# SF16_POWER.net
KiCad netlist of a schematic drawn in Altium Designer
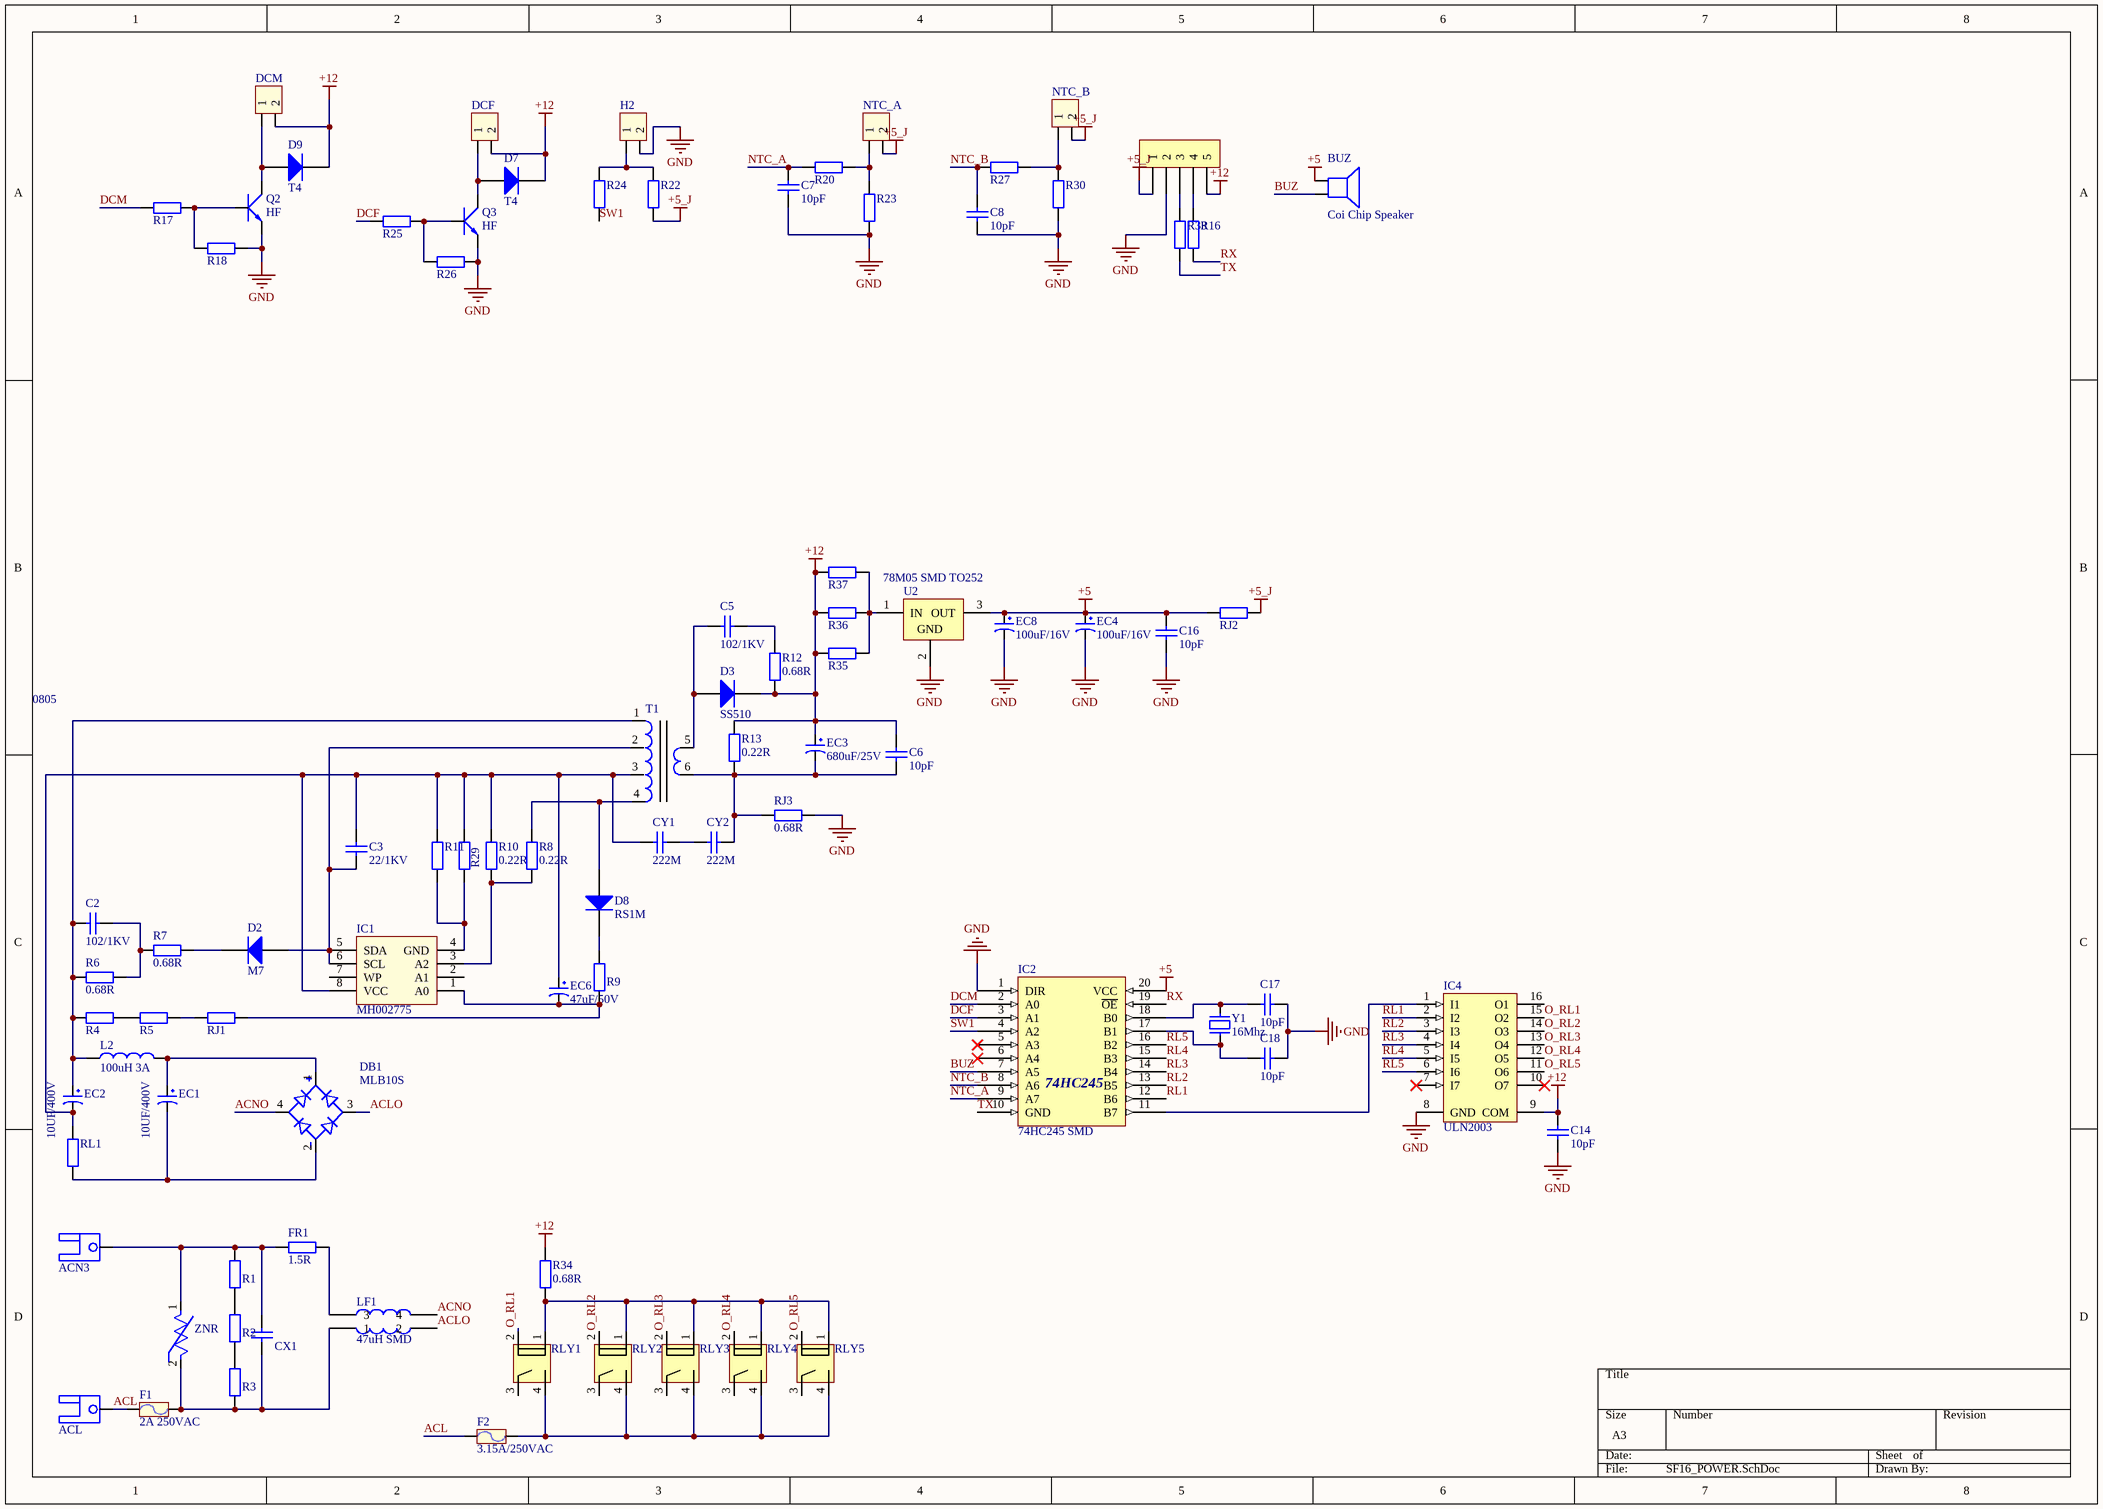
[diagram p0: SF16_POWER.SchDoc]

(export (version "E")
  (design (tool "Eeschema 10.0.6"))
  (components
    (comp (ref "ACL")
      (value "1217861-1")
      (footprint "CON1_P192_70D137_TH_ST")
      (description "1 Pins, 1 Row 256mil Pitch, Straight, Male")
      (fields
        (field (name "MANUFACTURER") "TE Connectivity")
        (field (name "MATING PART NUMBER") "2-520183-2")
      )
      (libsource (lib "Connector") (part "CON-PLG-SPADE_1X1-256-ST-TH"))
    )
    (comp (ref "ACN3")
      (value "1217861-1")
      (footprint "CON1_P192_70D137_TH_ST")
      (description "1 Pins, 1 Row 256mil Pitch, Straight, Male")
      (fields
        (field (name "MANUFACTURER") "TE Connectivity")
        (field (name "MATING PART NUMBER") "2-520183-2")
      )
      (libsource (lib "Connector") (part "CON-PLG-SPADE_1X1-256-ST-TH"))
    )
    (comp (ref "BUZ")
      (value "Coi Chip Speaker")
      (footprint "Coi 14mm")
      (description "Còi chip")
      (libsource (lib "Component") (part "Coi 14mm"))
    )
    (comp (ref "C2")
      (value "102/1KV")
      (footprint "TU GOM CAO AP")
      (description "Cắm")
      (libsource (lib "Tu dien") (part "Tu gom CAO AP"))
    )
    (comp (ref "C3")
      (value "22/1KV")
      (footprint "TU GOM CAO AP")
      (description "Cắm")
      (libsource (lib "Tu dien") (part "Tu gom CAO AP"))
    )
    (comp (ref "C5")
      (value "102/1KV")
      (footprint "TU GOM CAO AP")
      (description "Cắm")
      (libsource (lib "Tu dien") (part "Tu gom CAO AP"))
    )
    (comp (ref "C6")
      (value "10pF")
      (footprint "tu 0805")
      (description "Dán")
      (libsource (lib "Tu dien") (part "Tu 0805 10pF 50V 10%"))
    )
    (comp (ref "C7")
      (value "10pF")
      (footprint "tu 0805")
      (description "Dán")
      (libsource (lib "Tu dien") (part "Tu 0805 10pF 50V 10%"))
    )
    (comp (ref "C8")
      (value "10pF")
      (footprint "tu 0805")
      (description "Dán")
      (libsource (lib "Tu dien") (part "Tu 0805 10pF 50V 10%"))
    )
    (comp (ref "C14")
      (value "10pF")
      (footprint "tu 0805")
      (description "Dán")
      (libsource (lib "Tu dien") (part "Tu 0805 10pF 50V 10%"))
    )
    (comp (ref "C16")
      (value "10pF")
      (footprint "tu 0805")
      (description "Dán")
      (libsource (lib "Tu dien") (part "Tu 0805 10pF 50V 10%"))
    )
    (comp (ref "C17")
      (value "10pF")
      (footprint "tu 0805")
      (description "Dán")
      (libsource (lib "Tu dien") (part "Tu 0805 10pF 50V 10%"))
    )
    (comp (ref "C18")
      (value "10pF")
      (footprint "tu 0805")
      (description "Dán")
      (libsource (lib "Tu dien") (part "Tu 0805 10pF 50V 10%"))
    )
    (comp (ref "CX1")
      (value "0.1")
      (footprint "Tu vuong 10mm")
      (description "Cắm")
      (libsource (lib "Tu dien") (part "Tu MKP X2 0.1uF 275VAC 10MM"))
    )
    (comp (ref "CY1")
      (value "222M")
      (footprint "TU GOM CAO AP 222M")
      (description "Cắm")
      (libsource (lib "Tu dien") (part "Tu gom CAO AP 222M"))
    )
    (comp (ref "CY2")
      (value "222M")
      (footprint "TU GOM CAO AP 222M")
      (description "Cắm")
      (libsource (lib "Tu dien") (part "Tu gom CAO AP 222M"))
    )
    (comp (ref "D2")
      (value "M7")
      (footprint "DIODE SMA")
      (description "Dán")
      (libsource (lib "Diode") (part "Diode M7 1N4007 SMD 1A 1000V"))
    )
    (comp (ref "D3")
      (value "SS510")
      (footprint "DIODE SMA")
      (description "Dán")
      (libsource (lib "Diode") (part "Diode SS34 ( 1N5822 )"))
    )
    (comp (ref "D7")
      (value "T4")
      (footprint "DIODE SOD-123")
      (description "Dán")
      (libsource (lib "Diode") (part "Diode S4"))
    )
    (comp (ref "D8")
      (value "RS1M")
      (footprint "DIODE SMA")
      (description "Dán")
      (libsource (lib "Diode") (part "Diode SS34 ( 1N5822 )"))
    )
    (comp (ref "D9")
      (value "T4")
      (footprint "DIODE SOD-123")
      (description "Dán")
      (libsource (lib "Diode") (part "Diode S4"))
    )
    (comp (ref "DB1")
      (value "MLB10S")
      (footprint "MBLS-1")
      (description "DÁN")
      (libsource (lib "Diode") (part "MLB10S"))
    )
    (comp (ref "DCF")
      (value "Header 2P 2.54 Duc Thang")
      (footprint "XH2.54M-2")
      (description "Cắm")
      (libsource (lib "Header") (part "Header 2P 2.54 Duc Thang"))
    )
    (comp (ref "DCM")
      (value "Header 2P 2.54 Duc Thang")
      (footprint "XH2.54M-2")
      (description "Cắm")
      (libsource (lib "Header") (part "Header 2P 2.54 Duc Thang"))
    )
    (comp (ref "EC1")
      (value "10UF/400V")
      (footprint "tu hoa 10mm")
      (description "Cắm")
      (libsource (lib "Tu dien") (part "Tu Hoa 1000uF 10V 10x12"))
    )
    (comp (ref "EC2")
      (value "10UF/400V")
      (footprint "tu hoa 10mm")
      (description "Cắm")
      (libsource (lib "Tu dien") (part "Tu Hoa 1000uF 10V 10x12"))
    )
    (comp (ref "EC3")
      (value "680uF/25V")
      (footprint "tu hoa 10mm")
      (description "Cắm")
      (libsource (lib "Tu dien") (part "Tu Hoa 6.8uF 400V 10x17"))
    )
    (comp (ref "EC4")
      (value "100uF/16V")
      (footprint "tu hoa 5mm")
      (description "Cắm")
      (libsource (lib "Tu dien") (part "Tu Hoa 330uF 10V 6x11"))
    )
    (comp (ref "EC6")
      (value "47uF/50V")
      (footprint "tu hoa 5mm")
      (description "Cắm")
      (libsource (lib "Tu dien") (part "Tu Hoa 47uF 16V 5x10"))
    )
    (comp (ref "EC8")
      (value "100uF/16V")
      (footprint "tu hoa 5mm")
      (description "Cắm")
      (libsource (lib "Tu dien") (part "Tu Hoa 330uF 10V 6x11"))
    )
    (comp (ref "F1")
      (value "2A 250VAC")
      (footprint "Cau chi 2A 250V T2A250V")
      (description "Cắm")
      (libsource (lib "Component") (part "Cau chi 2A 250V T2A250V"))
    )
    (comp (ref "F2")
      (value "3.15A/250VAC")
      (footprint "Cau Chi 250V")
      (description "Cắm")
      (libsource (lib "Component") (part "Cau chi 2A 250V T2A250V"))
    )
    (comp (ref "FR1")
      (value "1.5R")
      (footprint "TRO CAU CHI DUNG")
      (description "Cắm")
      (libsource (lib "Dien Tro") (part "Tro Vach 2W"))
    )
    (comp (ref "H2")
      (value "Header 2P 2.54 Duc Thang")
      (footprint "XH2.54M-2")
      (description "Cắm")
      (libsource (lib "Header") (part "Header 2P 2.54 Duc Thang"))
    )
    (comp (ref "H5")
      (value "Header 5P 2.54 DT")
      (footprint "XH2.54M-5")
      (description "Cắm")
      (libsource (lib "Header") (part "Header 5P 2.54 DT"))
    )
    (comp (ref "IC1")
      (value "MH002775")
      (footprint "DIP8")
      (description "Cắm")
      (libsource (lib "IC") (part "AT24C01 DIP8 EEPROM"))
    )
    (comp (ref "IC2")
      (value "74HC245 SMD")
      (footprint "SOP 20")
      (description "Dán")
      (libsource (lib "IC") (part "74HC245 SMD"))
    )
    (comp (ref "IC4")
      (value "ULN2003")
      (footprint "SOP 16")
      (description "Dán")
      (libsource (lib "IC") (part "ULN2003A SMD"))
    )
    (comp (ref "L2")
      (value "100uH 3A")
      (footprint "CUON CAM - duplicate")
      (description "Dán")
      (libsource (lib "Cuon Cam") (part "CUON CAM VACH DUNG"))
    )
    (comp (ref "LF1")
      (value "47uH SMD")
      (footprint "Cuon Cam AC-AC")
      (description "Dán")
      (libsource (lib "Cuon Cam") (part "CUON CAM AC_AC"))
    )
    (comp (ref "NTC_A")
      (value "Header 2P 2.54 Duc Thang")
      (footprint "XH2.54M-2")
      (description "Cắm")
      (libsource (lib "Header") (part "Header 2P 2.54 Duc Thang"))
    )
    (comp (ref "NTC_B")
      (value "Header 2P 2.54 Duc Thang")
      (footprint "XH2.54M-2")
      (description "Cắm")
      (libsource (lib "Header") (part "Header 2P 2.54 Duc Thang"))
    )
    (comp (ref "Q2")
      (value "HF")
      (footprint "SOT-23")
      (description "Cắm")
      (libsource (lib "TranFet") (part "C1815 SOT23 TRANS NPN 0.15A 50V"))
    )
    (comp (ref "Q3")
      (value "HF")
      (footprint "SOT-23")
      (description "Cắm")
      (libsource (lib "TranFet") (part "C1815 SOT23 TRANS NPN 0.15A 50V"))
    )
    (comp (ref "R1")
      (value "0.68R")
      (footprint "tro smd 1206")
      (description "Dán")
      (libsource (lib "Dien Tro") (part "Tro 1206"))
    )
    (comp (ref "R2")
      (value "0.68R")
      (footprint "tro smd 1206")
      (description "Dán")
      (libsource (lib "Dien Tro") (part "Tro 1206"))
    )
    (comp (ref "R3")
      (value "0.68R")
      (footprint "tro smd 1206")
      (description "Dán")
      (libsource (lib "Dien Tro") (part "Tro 1206"))
    )
    (comp (ref "R4")
      (value "0.68R")
      (footprint "tro smd 1206")
      (description "Dán")
      (libsource (lib "Dien Tro") (part "Tro 1206"))
    )
    (comp (ref "R5")
      (value "0.68R")
      (footprint "tro smd 1206")
      (description "Dán")
      (libsource (lib "Dien Tro") (part "Tro 1206"))
    )
    (comp (ref "R6")
      (value "0.68R")
      (footprint "tro smd 1206")
      (description "Dán")
      (libsource (lib "Dien Tro") (part "Tro 1206"))
    )
    (comp (ref "R7")
      (value "0.68R")
      (footprint "tro smd 1206")
      (description "Dán")
      (libsource (lib "Dien Tro") (part "Tro 1206"))
    )
    (comp (ref "R8")
      (value "0.22R")
      (footprint "tro smd 0805")
      (description "Dán")
      (libsource (lib "Dien Tro") (part "Tro 0805"))
    )
    (comp (ref "R9")
      (value "0.68R")
      (footprint "tro smd 1206")
      (description "Dán")
      (libsource (lib "Dien Tro") (part "Tro 1206"))
    )
    (comp (ref "R10")
      (value "0.22R")
      (footprint "tro smd 0805")
      (description "Dán")
      (libsource (lib "Dien Tro") (part "Tro 0805"))
    )
    (comp (ref "R11")
      (value "0.68R")
      (footprint "tro smd 1206")
      (description "Dán")
      (libsource (lib "Dien Tro") (part "Tro 1206"))
    )
    (comp (ref "R12")
      (value "0.68R")
      (footprint "tro smd 1206")
      (description "Dán")
      (libsource (lib "Dien Tro") (part "Tro 1206"))
    )
    (comp (ref "R13")
      (value "0.22R")
      (footprint "tro smd 0805")
      (description "Dán")
      (libsource (lib "Dien Tro") (part "Tro 0805"))
    )
    (comp (ref "R16")
      (value "0.22R")
      (footprint "tro smd 0805")
      (description "Dán")
      (libsource (lib "Dien Tro") (part "Tro 0805"))
    )
    (comp (ref "R17")
      (value "0.68R")
      (footprint "tro smd 1206")
      (description "Dán")
      (libsource (lib "Dien Tro") (part "Tro 1206"))
    )
    (comp (ref "R18")
      (value "0.22R")
      (footprint "tro smd 0805")
      (description "Dán")
      (libsource (lib "Dien Tro") (part "Tro 0805"))
    )
    (comp (ref "R20")
      (value "0.22R")
      (footprint "tro smd 0805")
      (description "Dán")
      (libsource (lib "Dien Tro") (part "Tro 0805"))
    )
    (comp (ref "R22")
      (value "0.22R")
      (footprint "tro smd 0805")
      (description "Dán")
      (libsource (lib "Dien Tro") (part "Tro 0805"))
    )
    (comp (ref "R23")
      (value "0.22R")
      (footprint "tro smd 0805")
      (description "Dán")
      (libsource (lib "Dien Tro") (part "Tro 0805"))
    )
    (comp (ref "R24")
      (value "0.22R")
      (footprint "tro smd 0805")
      (description "Dán")
      (libsource (lib "Dien Tro") (part "Tro 0805"))
    )
    (comp (ref "R25")
      (value "0.68R")
      (footprint "tro smd 1206")
      (description "Dán")
      (libsource (lib "Dien Tro") (part "Tro 1206"))
    )
    (comp (ref "R26")
      (value "0.22R")
      (footprint "tro smd 0805")
      (description "Dán")
      (libsource (lib "Dien Tro") (part "Tro 0805"))
    )
    (comp (ref "R27")
      (value "0.22R")
      (footprint "tro smd 0805")
      (description "Dán")
      (libsource (lib "Dien Tro") (part "Tro 0805"))
    )
    (comp (ref "R29")
      (value "0.68R")
      (footprint "tro smd 1206")
      (description "Dán")
      (libsource (lib "Dien Tro") (part "Tro 1206"))
    )
    (comp (ref "R30")
      (value "0.22R")
      (footprint "tro smd 0805")
      (description "Dán")
      (libsource (lib "Dien Tro") (part "Tro 0805"))
    )
    (comp (ref "R33")
      (value "0.68R")
      (footprint "tro smd 1206")
      (description "Dán")
      (libsource (lib "Dien Tro") (part "Tro 1206"))
    )
    (comp (ref "R34")
      (value "0.68R")
      (footprint "tro smd 1206")
      (description "Dán")
      (libsource (lib "Dien Tro") (part "Tro 1206"))
    )
    (comp (ref "R35")
      (value "0.68R")
      (footprint "tro smd 1206")
      (description "Dán")
      (libsource (lib "Dien Tro") (part "Tro 1206"))
    )
    (comp (ref "R36")
      (value "0.68R")
      (footprint "tro smd 1206")
      (description "Dán")
      (libsource (lib "Dien Tro") (part "Tro 1206"))
    )
    (comp (ref "R37")
      (value "0.68R")
      (footprint "tro smd 1206")
      (description "Dán")
      (libsource (lib "Dien Tro") (part "Tro 1206"))
    )
    (comp (ref "RJ1")
      (value "0.68R")
      (footprint "tro smd 1206")
      (description "Dán")
      (libsource (lib "Dien Tro") (part "Tro 1206"))
    )
    (comp (ref "RJ2")
      (value "0.68R")
      (footprint "tro smd 1206")
      (description "Dán")
      (libsource (lib "Dien Tro") (part "Tro 1206"))
    )
    (comp (ref "RJ3")
      (value "0.68R")
      (footprint "tro smd 1206")
      (description "Dán")
      (libsource (lib "Dien Tro") (part "Tro 1206"))
    )
    (comp (ref "RL1")
      (value "0.68R")
      (footprint "tro smd 1206")
      (description "Dán")
      (libsource (lib "Dien Tro") (part "Tro 1206"))
    )
    (comp (ref "RLY1")
      (value "Relay JZC-8F-1H")
      (footprint "Relay 4 chan JZC-8F")
      (description "Relay 4 chan HF46F")
      (libsource (lib "Component") (part "Relay 4 chan JZC-8F-1H"))
    )
    (comp (ref "RLY2")
      (value "Relay JZC-8F-1H")
      (footprint "Relay 4 chan JZC-8F")
      (description "Relay 4 chan HF46F")
      (libsource (lib "Component") (part "Relay 4 chan JZC-8F-1H"))
    )
    (comp (ref "RLY3")
      (value "Relay JZC-8F-1H")
      (footprint "Relay 4 chan JZC-8F")
      (description "Relay 4 chan HF46F")
      (libsource (lib "Component") (part "Relay 4 chan JZC-8F-1H"))
    )
    (comp (ref "RLY4")
      (value "Relay JZC-8F-1H")
      (footprint "Relay 4 chan JZC-8F")
      (description "Relay 4 chan HF46F")
      (libsource (lib "Component") (part "Relay 4 chan JZC-8F-1H"))
    )
    (comp (ref "RLY5")
      (value "Relay JZC-8F-1H")
      (footprint "Relay 4 chan JZC-8F")
      (description "Relay 4 chan HF46F")
      (libsource (lib "Component") (part "Relay 4 chan JZC-8F-1H"))
    )
    (comp (ref "T1")
      (value "Bien ap")
      (footprint "BIEN AP EE1610-12V1.1A")
      (libsource (lib "Component") (part "Bien ap"))
    )
    (comp (ref "U2")
      (value "78M05 SMD TO252")
      (footprint "TO252")
      (description "Dán")
      (libsource (lib "IC") (part "78M05 SMD TO252"))
    )
    (comp (ref "Y1")
      (value "16Mhz")
      (footprint "Thach Anh 2 Chan 32,768 KHz")
      (description "Crystal For all Crystal 2pin.")
      (libsource (lib "Component") (part "Thach Anh 2 chan 32,768 Khz"))
    )
    (comp (ref "ZNR")
      (value "MOV-07D471KTR")
      (footprint "Tu MOV - duplicate")
      (description "Cam")
      (fields
        (field (name "OCTOPART") "https://octopart.com/mov-07d471ktr-bourns-19184728")
        (field (name "MANUFACTURER") "Bourns Inc.")
      )
      (libsource (lib "Tu dien") (part "Varistor 10D471K 470V"))
    )
  )
  (nets
    (net (code "1") (name "+5") (class "Default")
      (node (ref "BUZ") (pin "2") (pinfunction "2_2") (pintype "passive"))
      (node (ref "C16") (pin "2") (pinfunction "2_2") (pintype "passive"))
      (node (ref "EC4") (pin "1") (pinfunction "1_1") (pintype "passive"))
      (node (ref "EC8") (pin "1") (pinfunction "1_1") (pintype "passive"))
      (node (ref "IC2") (pin "20") (pinfunction "VCC_20") (pintype "input"))
      (node (ref "RJ2") (pin "1") (pinfunction "1_1") (pintype "passive"))
      (node (ref "U2") (pin "3") (pinfunction "OUT_3") (pintype "power_in"))
    )
    (net (code "2") (name "+5_J") (class "Default")
      (node (ref "H5") (pin "1") (pinfunction "1_1") (pintype "passive"))
      (node (ref "NTC_A") (pin "2") (pinfunction "2_2") (pintype "passive"))
      (node (ref "NTC_B") (pin "2") (pinfunction "2_2") (pintype "passive"))
      (node (ref "R22") (pin "1") (pinfunction "1_1") (pintype "passive"))
      (node (ref "RJ2") (pin "2") (pinfunction "2_2") (pintype "passive"))
    )
    (net (code "3") (name "+12") (class "Default")
      (node (ref "C14") (pin "1") (pinfunction "1_1") (pintype "passive"))
      (node (ref "C6") (pin "2") (pinfunction "2_2") (pintype "passive"))
      (node (ref "D3") (pin "2") (pinfunction "K_2") (pintype "passive"))
      (node (ref "D7") (pin "2") (pinfunction "K_2") (pintype "passive"))
      (node (ref "D9") (pin "2") (pinfunction "K_2") (pintype "passive"))
      (node (ref "DCF") (pin "2") (pinfunction "2_2") (pintype "passive"))
      (node (ref "DCM") (pin "2") (pinfunction "2_2") (pintype "passive"))
      (node (ref "EC3") (pin "1") (pinfunction "1_1") (pintype "passive"))
      (node (ref "H5") (pin "5") (pinfunction "5_5") (pintype "passive"))
      (node (ref "IC4") (pin "9") (pinfunction "COM_9") (pintype "passive"))
      (node (ref "R12") (pin "2") (pinfunction "2_2") (pintype "passive"))
      (node (ref "R13") (pin "1") (pinfunction "1_1") (pintype "passive"))
      (node (ref "R34") (pin "2") (pinfunction "2_2") (pintype "passive"))
      (node (ref "R35") (pin "2") (pinfunction "2_2") (pintype "passive"))
      (node (ref "R36") (pin "2") (pinfunction "2_2") (pintype "passive"))
      (node (ref "R37") (pin "2") (pinfunction "2_2") (pintype "passive"))
    )
    (net (code "4") (name "/ACL") (class "Default")
      (node (ref "ACL") (pin "1") (pinfunction "1_1") (pintype "passive"))
      (node (ref "F1") (pin "1") (pinfunction "1_1") (pintype "passive"))
      (node (ref "F2") (pin "1") (pinfunction "1_1") (pintype "passive"))
    )
    (net (code "5") (name "/ACLO") (class "Default")
      (node (ref "DB1") (pin "3") (pinfunction "AC2_3") (pintype "passive"))
      (node (ref "LF1") (pin "2") (pinfunction "2_2") (pintype "passive"))
    )
    (net (code "6") (name "/ACNO") (class "Default")
      (node (ref "DB1") (pin "4") (pinfunction "AC1_4") (pintype "passive"))
      (node (ref "LF1") (pin "4") (pinfunction "4_4") (pintype "passive"))
    )
    (net (code "7") (name "/BUZ") (class "Default")
      (node (ref "BUZ") (pin "1") (pinfunction "1_1") (pintype "passive"))
      (node (ref "IC2") (pin "7") (pinfunction "A5_7") (pintype "input"))
    )
    (net (code "8") (name "/DCF") (class "Default")
      (node (ref "IC2") (pin "3") (pinfunction "A1_3") (pintype "input"))
      (node (ref "R25") (pin "1") (pinfunction "1_1") (pintype "passive"))
    )
    (net (code "9") (name "/DCM") (class "Default")
      (node (ref "IC2") (pin "2") (pinfunction "A0_2") (pintype "input"))
      (node (ref "R17") (pin "1") (pinfunction "1_1") (pintype "passive"))
    )
    (net (code "10") (name "/NTC_A") (class "Default")
      (node (ref "C7") (pin "2") (pinfunction "2_2") (pintype "passive"))
      (node (ref "IC2") (pin "9") (pinfunction "A7_9") (pintype "input"))
      (node (ref "R20") (pin "1") (pinfunction "1_1") (pintype "passive"))
    )
    (net (code "11") (name "/NTC_B") (class "Default")
      (node (ref "C8") (pin "2") (pinfunction "2_2") (pintype "passive"))
      (node (ref "IC2") (pin "8") (pinfunction "A6_8") (pintype "input"))
      (node (ref "R27") (pin "1") (pinfunction "1_1") (pintype "passive"))
    )
    (net (code "12") (name "/O_RL1") (class "Default")
      (node (ref "IC4") (pin "15") (pinfunction "O2_15") (pintype "open_collector"))
      (node (ref "RLY1") (pin "2") (pintype "passive"))
    )
    (net (code "13") (name "/O_RL2") (class "Default")
      (node (ref "IC4") (pin "14") (pinfunction "O3_14") (pintype "open_collector"))
      (node (ref "RLY2") (pin "2") (pintype "passive"))
    )
    (net (code "14") (name "/O_RL3") (class "Default")
      (node (ref "IC4") (pin "13") (pinfunction "O4_13") (pintype "open_collector"))
      (node (ref "RLY3") (pin "2") (pintype "passive"))
    )
    (net (code "15") (name "/O_RL4") (class "Default")
      (node (ref "IC4") (pin "12") (pinfunction "O5_12") (pintype "open_collector"))
      (node (ref "RLY4") (pin "2") (pintype "passive"))
    )
    (net (code "16") (name "/O_RL5") (class "Default")
      (node (ref "IC4") (pin "11") (pinfunction "O6_11") (pintype "open_collector"))
      (node (ref "RLY5") (pin "2") (pintype "passive"))
    )
    (net (code "17") (name "/RL1") (class "Default")
      (node (ref "IC2") (pin "12") (pinfunction "B6_12") (pintype "output"))
      (node (ref "IC4") (pin "2") (pinfunction "I2_2") (pintype "input"))
    )
    (net (code "18") (name "/RL2") (class "Default")
      (node (ref "IC2") (pin "13") (pinfunction "B5_13") (pintype "output"))
      (node (ref "IC4") (pin "3") (pinfunction "I3_3") (pintype "input"))
    )
    (net (code "19") (name "/RL3") (class "Default")
      (node (ref "IC2") (pin "14") (pinfunction "B4_14") (pintype "output"))
      (node (ref "IC4") (pin "4") (pinfunction "I4_4") (pintype "input"))
    )
    (net (code "20") (name "/RL4") (class "Default")
      (node (ref "IC2") (pin "15") (pinfunction "B3_15") (pintype "output"))
      (node (ref "IC4") (pin "5") (pinfunction "I5_5") (pintype "input"))
    )
    (net (code "21") (name "/RL5") (class "Default")
      (node (ref "IC2") (pin "16") (pinfunction "B2_16") (pintype "output"))
      (node (ref "IC4") (pin "6") (pinfunction "I6_6") (pintype "input"))
    )
    (net (code "22") (name "/RX") (class "Default")
      (node (ref "IC2") (pin "19") (pinfunction "~{OE}_19") (pintype "input"))
      (node (ref "R16") (pin "1") (pinfunction "1_1") (pintype "passive"))
    )
    (net (code "23") (name "/SW1") (class "Default")
      (node (ref "IC2") (pin "4") (pinfunction "A2_4") (pintype "input"))
      (node (ref "R24") (pin "1") (pinfunction "1_1") (pintype "passive"))
    )
    (net (code "24") (name "/TX") (class "Default")
      (node (ref "IC2") (pin "10") (pinfunction "GND_10") (pintype "input"))
      (node (ref "R33") (pin "1") (pinfunction "1_1") (pintype "passive"))
    )
    (net (code "25") (name "GND") (class "Default")
      (node (ref "C14") (pin "2") (pinfunction "2_2") (pintype "passive"))
      (node (ref "C16") (pin "1") (pinfunction "1_1") (pintype "passive"))
      (node (ref "C17") (pin "2") (pinfunction "2_2") (pintype "passive"))
      (node (ref "C18") (pin "1") (pinfunction "1_1") (pintype "passive"))
      (node (ref "C7") (pin "1") (pinfunction "1_1") (pintype "passive"))
      (node (ref "C8") (pin "1") (pinfunction "1_1") (pintype "passive"))
      (node (ref "EC4") (pin "2") (pinfunction "2_2") (pintype "passive"))
      (node (ref "EC8") (pin "2") (pinfunction "2_2") (pintype "passive"))
      (node (ref "H2") (pin "2") (pinfunction "2_2") (pintype "passive"))
      (node (ref "H5") (pin "2") (pinfunction "2_2") (pintype "passive"))
      (node (ref "IC2") (pin "1") (pinfunction "DIR_1") (pintype "input"))
      (node (ref "IC4") (pin "8") (pinfunction "GND_8") (pintype "power_in"))
      (node (ref "Q2") (pin "2") (pinfunction "E_2") (pintype "passive"))
      (node (ref "Q3") (pin "2") (pinfunction "E_2") (pintype "passive"))
      (node (ref "R18") (pin "2") (pinfunction "2_2") (pintype "passive"))
      (node (ref "R23") (pin "1") (pinfunction "1_1") (pintype "passive"))
      (node (ref "R26") (pin "2") (pinfunction "2_2") (pintype "passive"))
      (node (ref "R30") (pin "1") (pinfunction "1_1") (pintype "passive"))
      (node (ref "RJ3") (pin "1") (pinfunction "1_1") (pintype "passive"))
      (node (ref "U2") (pin "2") (pinfunction "GND_2") (pintype "power_in"))
    )
    (net (code "26") (name "Net-(ACN3-Pad1)") (class "Default")
      (node (ref "ACN3") (pin "1") (pinfunction "1_1") (pintype "passive"))
      (node (ref "CX1") (pin "2") (pinfunction "2_2") (pintype "passive"))
      (node (ref "FR1") (pin "2") (pinfunction "2_2") (pintype "passive"))
      (node (ref "R1") (pin "2") (pinfunction "2_2") (pintype "passive"))
      (node (ref "ZNR") (pin "1") (pinfunction "1_1") (pintype "passive"))
    )
    (net (code "27") (name "Net-(C2-Pad1)") (class "Default")
      (node (ref "C2") (pin "1") (pinfunction "1_1") (pintype "passive"))
      (node (ref "R6") (pin "2") (pinfunction "2_2") (pintype "passive"))
      (node (ref "R7") (pin "1") (pinfunction "1_1") (pintype "passive"))
    )
    (net (code "28") (name "Net-(C2-Pad2)") (class "Default")
      (node (ref "C2") (pin "2") (pinfunction "2_2") (pintype "passive"))
      (node (ref "EC2") (pin "1") (pinfunction "1_1") (pintype "passive"))
      (node (ref "L2") (pin "2") (pinfunction "2_2") (pintype "passive"))
      (node (ref "R4") (pin "2") (pinfunction "2_2") (pintype "passive"))
      (node (ref "R6") (pin "1") (pinfunction "1_1") (pintype "passive"))
      (node (ref "T1") (pin "1") (pinfunction "4_1") (pintype "passive"))
    )
    (net (code "29") (name "Net-(C5-Pad1)") (class "Default")
      (node (ref "C5") (pin "1") (pinfunction "1_1") (pintype "passive"))
      (node (ref "R12") (pin "1") (pinfunction "1_1") (pintype "passive"))
    )
    (net (code "30") (name "Net-(CX1-Pad1)") (class "Default")
      (node (ref "CX1") (pin "1") (pinfunction "1_1") (pintype "passive"))
      (node (ref "F1") (pin "2") (pinfunction "2_2") (pintype "passive"))
      (node (ref "LF1") (pin "1") (pinfunction "1_1") (pintype "passive"))
      (node (ref "R3") (pin "1") (pinfunction "1_1") (pintype "passive"))
      (node (ref "ZNR") (pin "2") (pinfunction "2_2") (pintype "passive"))
    )
    (net (code "31") (name "Net-(CY1-Pad1)") (class "Default")
      (node (ref "CY1") (pin "1") (pinfunction "1_1") (pintype "passive"))
      (node (ref "CY2") (pin "2") (pinfunction "2_2") (pintype "passive"))
    )
    (net (code "32") (name "Net-(D2-A)") (class "Default")
      (node (ref "C3") (pin "1") (pinfunction "1_1") (pintype "passive"))
      (node (ref "D2") (pin "1") (pinfunction "A_1") (pintype "passive"))
      (node (ref "IC1") (pin "5") (pinfunction "SDA_5") (pintype "passive"))
      (node (ref "IC1") (pin "6") (pinfunction "SCL_6") (pintype "passive"))
      (node (ref "T1") (pin "2") (pinfunction "4_2") (pintype "passive"))
    )
    (net (code "33") (name "Net-(D2-K)") (class "Default")
      (node (ref "D2") (pin "2") (pinfunction "K_2") (pintype "passive"))
      (node (ref "R7") (pin "2") (pinfunction "2_2") (pintype "passive"))
    )
    (net (code "34") (name "Net-(D3-A)") (class "Default")
      (node (ref "C5") (pin "2") (pinfunction "2_2") (pintype "passive"))
      (node (ref "D3") (pin "1") (pinfunction "A_1") (pintype "passive"))
      (node (ref "T1") (pin "5") (pinfunction "4_5") (pintype "passive"))
    )
    (net (code "35") (name "Net-(D7-A)") (class "Default")
      (node (ref "D7") (pin "1") (pinfunction "A_1") (pintype "passive"))
      (node (ref "DCF") (pin "1") (pinfunction "1_1") (pintype "passive"))
      (node (ref "Q3") (pin "3") (pinfunction "C_3") (pintype "passive"))
    )
    (net (code "36") (name "Net-(D8-A)") (class "Default")
      (node (ref "D8") (pin "1") (pinfunction "A_1") (pintype "passive"))
      (node (ref "R8") (pin "1") (pinfunction "1_1") (pintype "passive"))
      (node (ref "T1") (pin "4") (pinfunction "4_4") (pintype "passive"))
    )
    (net (code "37") (name "Net-(D8-K)") (class "Default")
      (node (ref "D8") (pin "2") (pinfunction "K_2") (pintype "passive"))
      (node (ref "R9") (pin "1") (pinfunction "1_1") (pintype "passive"))
    )
    (net (code "38") (name "Net-(D9-A)") (class "Default")
      (node (ref "D9") (pin "1") (pinfunction "A_1") (pintype "passive"))
      (node (ref "DCM") (pin "1") (pinfunction "1_1") (pintype "passive"))
      (node (ref "Q2") (pin "3") (pinfunction "C_3") (pintype "passive"))
    )
    (net (code "39") (name "Net-(DB1-NEG)") (class "Default")
      (node (ref "DB1") (pin "2") (pinfunction "NEG_2") (pintype "passive"))
      (node (ref "EC1") (pin "2") (pinfunction "2_2") (pintype "passive"))
      (node (ref "RL1") (pin "1") (pinfunction "1_1") (pintype "passive"))
    )
    (net (code "40") (name "Net-(DB1-POS)") (class "Default")
      (node (ref "DB1") (pin "1") (pinfunction "POS_1") (pintype "passive"))
      (node (ref "EC1") (pin "1") (pinfunction "1_1") (pintype "passive"))
      (node (ref "L2") (pin "1") (pinfunction "1_1") (pintype "passive"))
    )
    (net (code "41") (name "Net-(F2-Pad2)") (class "Default")
      (node (ref "F2") (pin "2") (pinfunction "2_2") (pintype "passive"))
      (node (ref "RLY1") (pin "4") (pinfunction "AC/DC_4") (pintype "passive"))
      (node (ref "RLY2") (pin "4") (pinfunction "AC/DC_4") (pintype "passive"))
      (node (ref "RLY3") (pin "4") (pinfunction "AC/DC_4") (pintype "passive"))
      (node (ref "RLY4") (pin "4") (pinfunction "AC/DC_4") (pintype "passive"))
      (node (ref "RLY5") (pin "4") (pinfunction "AC/DC_4") (pintype "passive"))
    )
    (net (code "42") (name "Net-(FR1-Pad1)") (class "Default")
      (node (ref "FR1") (pin "1") (pinfunction "1_1") (pintype "passive"))
      (node (ref "LF1") (pin "3") (pinfunction "3_3") (pintype "passive"))
    )
    (net (code "43") (name "Net-(H2-Pad1)") (class "Default")
      (node (ref "H2") (pin "1") (pinfunction "1_1") (pintype "passive"))
      (node (ref "R22") (pin "2") (pinfunction "2_2") (pintype "passive"))
      (node (ref "R24") (pin "2") (pinfunction "2_2") (pintype "passive"))
    )
    (net (code "44") (name "Net-(H5-Pad3)") (class "Default")
      (node (ref "H5") (pin "3") (pinfunction "3_3") (pintype "passive"))
      (node (ref "R33") (pin "2") (pinfunction "2_2") (pintype "passive"))
    )
    (net (code "45") (name "Net-(H5-Pad4)") (class "Default")
      (node (ref "H5") (pin "4") (pinfunction "4_4") (pintype "passive"))
      (node (ref "R16") (pin "2") (pinfunction "2_2") (pintype "passive"))
    )
    (net (code "46") (name "Net-(IC1-A0)") (class "Default")
      (node (ref "EC6") (pin "2") (pinfunction "2_2") (pintype "passive"))
      (node (ref "IC1") (pin "1") (pinfunction "A0_1") (pintype "passive"))
      (node (ref "R9") (pin "2") (pinfunction "2_2") (pintype "passive"))
      (node (ref "RJ1") (pin "1") (pinfunction "1_1") (pintype "passive"))
    )
    (net (code "47") (name "Net-(IC1-A2)") (class "Default")
      (node (ref "IC1") (pin "3") (pinfunction "A2_3") (pintype "passive"))
      (node (ref "R10") (pin "2") (pinfunction "2_2") (pintype "passive"))
      (node (ref "R8") (pin "2") (pinfunction "2_2") (pintype "passive"))
    )
    (net (code "48") (name "Net-(IC1-GND)") (class "Default")
      (node (ref "IC1") (pin "4") (pinfunction "GND_4") (pintype "power_in"))
      (node (ref "R11") (pin "1") (pinfunction "1_1") (pintype "passive"))
      (node (ref "R29") (pin "1") (pinfunction "1_1") (pintype "passive"))
    )
    (net (code "49") (name "Net-(IC1-VCC)") (class "Default")
      (node (ref "C3") (pin "2") (pinfunction "2_2") (pintype "passive"))
      (node (ref "CY1") (pin "2") (pinfunction "2_2") (pintype "passive"))
      (node (ref "EC2") (pin "2") (pinfunction "2_2") (pintype "passive"))
      (node (ref "EC6") (pin "1") (pinfunction "1_1") (pintype "passive"))
      (node (ref "IC1") (pin "8") (pinfunction "VCC_8") (pintype "power_in"))
      (node (ref "R10") (pin "1") (pinfunction "1_1") (pintype "passive"))
      (node (ref "R11") (pin "2") (pinfunction "2_2") (pintype "passive"))
      (node (ref "R29") (pin "2") (pinfunction "2_2") (pintype "passive"))
      (node (ref "RL1") (pin "2") (pinfunction "2_2") (pintype "passive"))
      (node (ref "T1") (pin "3") (pinfunction "4_3") (pintype "passive"))
    )
    (net (code "50") (name "Net-(IC2-B0)") (class "Default")
      (node (ref "C17") (pin "1") (pinfunction "1_1") (pintype "passive"))
      (node (ref "IC2") (pin "18") (pinfunction "B0_18") (pintype "output"))
      (node (ref "Y1") (pin "1") (pinfunction "1_1") (pintype "passive"))
    )
    (net (code "51") (name "Net-(IC2-B1)") (class "Default")
      (node (ref "C18") (pin "2") (pinfunction "2_2") (pintype "passive"))
      (node (ref "IC2") (pin "17") (pinfunction "B1_17") (pintype "output"))
      (node (ref "Y1") (pin "2") (pinfunction "2_2") (pintype "passive"))
    )
    (net (code "52") (name "Net-(IC2-B7)") (class "Default")
      (node (ref "IC2") (pin "11") (pinfunction "B7_11") (pintype "output"))
      (node (ref "IC4") (pin "1") (pinfunction "I1_1") (pintype "input"))
    )
    (net (code "53") (name "Net-(NTC_A-Pad1)") (class "Default")
      (node (ref "NTC_A") (pin "1") (pinfunction "1_1") (pintype "passive"))
      (node (ref "R20") (pin "2") (pinfunction "2_2") (pintype "passive"))
      (node (ref "R23") (pin "2") (pinfunction "2_2") (pintype "passive"))
    )
    (net (code "54") (name "Net-(NTC_B-Pad1)") (class "Default")
      (node (ref "NTC_B") (pin "1") (pinfunction "1_1") (pintype "passive"))
      (node (ref "R27") (pin "2") (pinfunction "2_2") (pintype "passive"))
      (node (ref "R30") (pin "2") (pinfunction "2_2") (pintype "passive"))
    )
    (net (code "55") (name "Net-(Q2-B)") (class "Default")
      (node (ref "Q2") (pin "1") (pinfunction "B_1") (pintype "passive"))
      (node (ref "R17") (pin "2") (pinfunction "2_2") (pintype "passive"))
      (node (ref "R18") (pin "1") (pinfunction "1_1") (pintype "passive"))
    )
    (net (code "56") (name "Net-(Q3-B)") (class "Default")
      (node (ref "Q3") (pin "1") (pinfunction "B_1") (pintype "passive"))
      (node (ref "R25") (pin "2") (pinfunction "2_2") (pintype "passive"))
      (node (ref "R26") (pin "1") (pinfunction "1_1") (pintype "passive"))
    )
    (net (code "57") (name "Net-(R1-Pad1)") (class "Default")
      (node (ref "R1") (pin "1") (pinfunction "1_1") (pintype "passive"))
      (node (ref "R2") (pin "2") (pinfunction "2_2") (pintype "passive"))
    )
    (net (code "58") (name "Net-(R2-Pad1)") (class "Default")
      (node (ref "R2") (pin "1") (pinfunction "1_1") (pintype "passive"))
      (node (ref "R3") (pin "2") (pinfunction "2_2") (pintype "passive"))
    )
    (net (code "59") (name "Net-(R4-Pad1)") (class "Default")
      (node (ref "R4") (pin "1") (pinfunction "1_1") (pintype "passive"))
      (node (ref "R5") (pin "2") (pinfunction "2_2") (pintype "passive"))
    )
    (net (code "60") (name "Net-(R5-Pad1)") (class "Default")
      (node (ref "R5") (pin "1") (pinfunction "1_1") (pintype "passive"))
      (node (ref "RJ1") (pin "2") (pinfunction "2_2") (pintype "passive"))
    )
    (net (code "61") (name "Net-(R34-Pad1)") (class "Default")
      (node (ref "R34") (pin "1") (pinfunction "1_1") (pintype "passive"))
      (node (ref "RLY1") (pin "1") (pintype "passive"))
      (node (ref "RLY2") (pin "1") (pintype "passive"))
      (node (ref "RLY3") (pin "1") (pintype "passive"))
      (node (ref "RLY4") (pin "1") (pintype "passive"))
      (node (ref "RLY5") (pin "1") (pintype "passive"))
    )
    (net (code "62") (name "Net-(T1-5)") (class "Default")
      (node (ref "C6") (pin "1") (pinfunction "1_1") (pintype "passive"))
      (node (ref "CY2") (pin "1") (pinfunction "1_1") (pintype "passive"))
      (node (ref "EC3") (pin "2") (pinfunction "2_2") (pintype "passive"))
      (node (ref "R13") (pin "2") (pinfunction "2_2") (pintype "passive"))
      (node (ref "RJ3") (pin "2") (pinfunction "2_2") (pintype "passive"))
      (node (ref "T1") (pin "6") (pinfunction "5_6") (pintype "passive"))
    )
    (net (code "63") (name "Net-(U2-IN)") (class "Default")
      (node (ref "R35") (pin "1") (pinfunction "1_1") (pintype "passive"))
      (node (ref "R36") (pin "1") (pinfunction "1_1") (pintype "passive"))
      (node (ref "R37") (pin "1") (pinfunction "1_1") (pintype "passive"))
      (node (ref "U2") (pin "1") (pinfunction "IN_1") (pintype "power_in"))
    )
    (net (code "64") (name "unconnected-(IC1-A1-Pad2)") (class "Default")
      (node (ref "IC1") (pin "2") (pinfunction "A1_2") (pintype "passive"))
    )
    (net (code "65") (name "unconnected-(IC1-WP-Pad7)") (class "Default")
      (node (ref "IC1") (pin "7") (pinfunction "WP_7") (pintype "passive"))
    )
    (net (code "66") (name "unconnected-(IC2-A3-Pad5)") (class "Default")
      (node (ref "IC2") (pin "5") (pinfunction "A3_5") (pintype "input+no_connect"))
    )
    (net (code "67") (name "unconnected-(IC2-A4-Pad6)") (class "Default")
      (node (ref "IC2") (pin "6") (pinfunction "A4_6") (pintype "input+no_connect"))
    )
    (net (code "68") (name "unconnected-(IC4-I7-Pad7)") (class "Default")
      (node (ref "IC4") (pin "7") (pinfunction "I7_7") (pintype "input+no_connect"))
    )
    (net (code "69") (name "unconnected-(IC4-O1-Pad16)") (class "Default")
      (node (ref "IC4") (pin "16") (pinfunction "O1_16") (pintype "open_collector"))
    )
    (net (code "70") (name "unconnected-(IC4-O7-Pad10)") (class "Default")
      (node (ref "IC4") (pin "10") (pinfunction "O7_10") (pintype "open_collector+no_connect"))
    )
    (net (code "71") (name "unconnected-(RLY1-AC{slash}DC-Pad3)") (class "Default")
      (node (ref "RLY1") (pin "3") (pinfunction "AC/DC_3") (pintype "passive"))
    )
    (net (code "72") (name "unconnected-(RLY2-AC{slash}DC-Pad3)") (class "Default")
      (node (ref "RLY2") (pin "3") (pinfunction "AC/DC_3") (pintype "passive"))
    )
    (net (code "73") (name "unconnected-(RLY3-AC{slash}DC-Pad3)") (class "Default")
      (node (ref "RLY3") (pin "3") (pinfunction "AC/DC_3") (pintype "passive"))
    )
    (net (code "74") (name "unconnected-(RLY4-AC{slash}DC-Pad3)") (class "Default")
      (node (ref "RLY4") (pin "3") (pinfunction "AC/DC_3") (pintype "passive"))
    )
    (net (code "75") (name "unconnected-(RLY5-AC{slash}DC-Pad3)") (class "Default")
      (node (ref "RLY5") (pin "3") (pinfunction "AC/DC_3") (pintype "passive"))
    )
  )
)
